# raw_input.net
KiCad netlist of a schematic drawn in Altium Designer
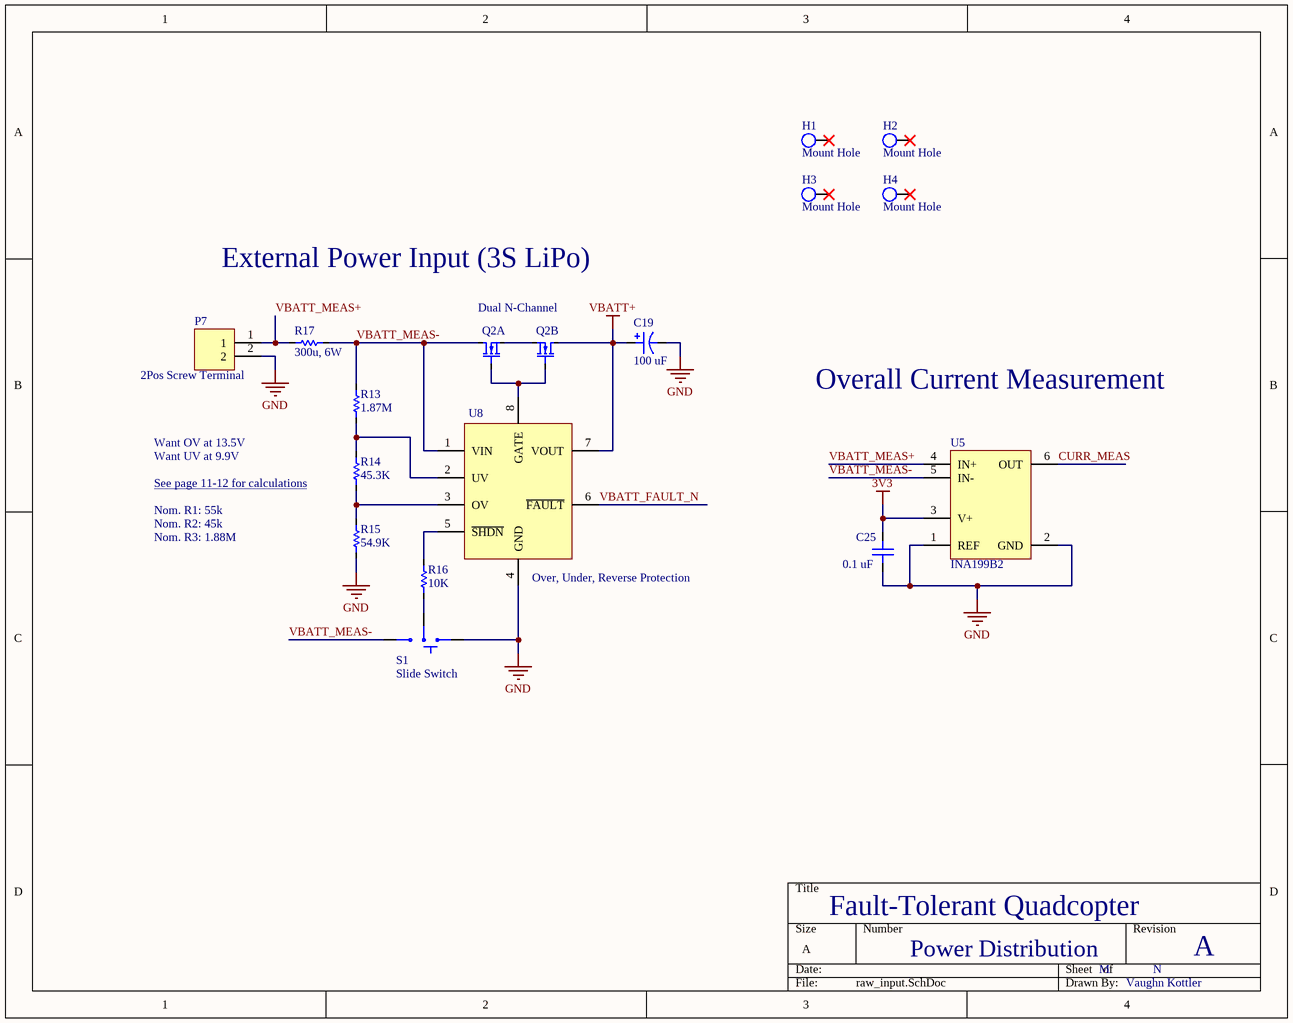
[diagram p0: raw_input.SchDoc]

(export (version "E")
  (design (tool "Eeschema 10.0.6"))
  (components
    (comp (ref "C19")
      (value "100 uF")
      (footprint "CAP-CAN-8.3x8.3")
      (description "±20%, 8.3mm x 8.3mm")
      (libsource (lib "passive") (part "CAP-CAN-100uF-25V"))
    )
    (comp (ref "C25")
      (value "0.1 uF")
      (footprint "CAP-CER-0805-SHORT")
      (description "10%, 0805")
      (libsource (lib "passive") (part "CAP-CER-0.1uF-25V"))
    )
    (comp (ref "H1")
      (value "Mount Hole")
      (footprint "4mm Mount Hole")
      (libsource (lib "connector") (part "Mount Hole"))
    )
    (comp (ref "H2")
      (value "Mount Hole")
      (footprint "4mm Mount Hole")
      (libsource (lib "connector") (part "Mount Hole"))
    )
    (comp (ref "H3")
      (value "Mount Hole")
      (footprint "4mm Mount Hole")
      (libsource (lib "connector") (part "Mount Hole"))
    )
    (comp (ref "H4")
      (value "Mount Hole")
      (footprint "4mm Mount Hole")
      (libsource (lib "connector") (part "Mount Hole"))
    )
    (comp (ref "P7")
      (value "2Pos Screw Terminal")
      (footprint "2Pos Screw Terminal")
      (description "0.2\" Pitch 1x2")
      (libsource (lib "connector") (part "2Pos Screw Terminal"))
    )
    (comp (ref "Q2")
      (value "Dual N-Channel")
      (footprint "PowerPAK 8x8L")
      (description "Dual N-Channel 40V 100A")
      (libsource (lib "ic") (part "SQJQ900E"))
    )
    (comp (ref "R13")
      (value "1.87M")
      (footprint "RES-0805")
      (description "1%, 0805")
      (libsource (lib "passive") (part "RES-1.87M-1/8W"))
    )
    (comp (ref "R14")
      (value "45.3K")
      (footprint "RES-0805")
      (description "1%, 0805")
      (libsource (lib "passive") (part "RES-45.3K-1/8W"))
    )
    (comp (ref "R15")
      (value "54.9K")
      (footprint "RES-0805")
      (description "1%, 0805")
      (libsource (lib "passive") (part "RES-54.9K-1/8W"))
    )
    (comp (ref "R16")
      (value "10K")
      (footprint "RES-0805")
      (description "0805")
      (libsource (lib "passive") (part "RES-10K-1/8W"))
    )
    (comp (ref "R17")
      (value "300u, 6W")
      (footprint "RES-SHNT-2512")
      (description "2512, 1%")
      (libsource (lib "passive") (part "RES-300u-6W"))
    )
    (comp (ref "S1")
      (value "Slide Switch")
      (footprint "SMT Slide Switch RA")
      (description "2mm Pitch")
      (libsource (lib "connector") (part "SMT Slide Switch"))
    )
    (comp (ref "U5")
      (value "INA199B2")
      (footprint "SC70")
      (description "100 V/V, Current-Shunt Monitor")
      (libsource (lib "ic") (part "INA199B2"))
    )
    (comp (ref "U8")
      (value "Over, Under, Reverse Protection")
      (footprint "SOT-23-8")
      (description "Overvoltage, Undervoltage and Reverse Supply Protection Controller")
      (libsource (lib "ic") (part "LTC4365"))
    )
  )
  (nets
    (net (code "1") (name "/CURR_MEAS") (class "Default")
      (node (ref "U5") (pin "6") (pinfunction "OUT_6") (pintype "passive"))
    )
    (net (code "2") (name "/VBATT_FAULT_N") (class "Default")
      (node (ref "U8") (pin "6") (pinfunction "~{FAULT}_6") (pintype "passive"))
    )
    (net (code "3") (name "/VBATT_MEAS+") (class "Default")
      (node (ref "P7") (pin "1") (pinfunction "1_1") (pintype "passive"))
      (node (ref "R17") (pin "1") (pinfunction "1_1") (pintype "passive"))
      (node (ref "U5") (pin "4") (pinfunction "IN+_4") (pintype "passive"))
    )
    (net (code "4") (name "/VBATT_MEAS-") (class "Default")
      (node (ref "Q2") (pin "D1") (pinfunction "D1_D1") (pintype "passive"))
      (node (ref "R13") (pin "2") (pinfunction "2_2") (pintype "passive"))
      (node (ref "R17") (pin "2") (pinfunction "2_2") (pintype "passive"))
      (node (ref "S1") (pin "3") (pinfunction "R_3") (pintype "passive"))
      (node (ref "U5") (pin "5") (pinfunction "IN-_5") (pintype "passive"))
      (node (ref "U8") (pin "1") (pinfunction "VIN_1") (pintype "passive"))
    )
    (net (code "5") (name "3V3") (class "Default")
      (node (ref "C25") (pin "2") (pinfunction "2_2") (pintype "passive"))
      (node (ref "U5") (pin "3") (pinfunction "V+_3") (pintype "passive"))
    )
    (net (code "6") (name "GND") (class "Default")
      (node (ref "C19") (pin "2") (pinfunction "2_2") (pintype "passive"))
      (node (ref "C25") (pin "1") (pinfunction "1_1") (pintype "passive"))
      (node (ref "P7") (pin "2") (pinfunction "2_2") (pintype "passive"))
      (node (ref "R15") (pin "1") (pinfunction "1_1") (pintype "passive"))
      (node (ref "S1") (pin "1") (pinfunction "L_1") (pintype "passive"))
      (node (ref "U5") (pin "1") (pinfunction "REF_1") (pintype "passive"))
      (node (ref "U5") (pin "2") (pinfunction "GND_2") (pintype "passive"))
      (node (ref "U8") (pin "4") (pinfunction "GND_4") (pintype "passive"))
    )
    (net (code "7") (name "Net-(Q2-PadS1)") (class "Default")
      (node (ref "Q2") (pin "S1") (pinfunction "S1_S1") (pintype "passive"))
      (node (ref "Q2") (pin "S2") (pinfunction "S2_S2") (pintype "passive"))
    )
    (net (code "8") (name "Net-(S1-COM)") (class "Default")
      (node (ref "R16") (pin "1") (pinfunction "1_1") (pintype "passive"))
      (node (ref "S1") (pin "2") (pinfunction "COM_2") (pintype "passive"))
    )
    (net (code "9") (name "Net-(U8-GATE)") (class "Default")
      (node (ref "Q2") (pin "G1") (pinfunction "G1_G1") (pintype "passive"))
      (node (ref "Q2") (pin "G2") (pinfunction "G2_G2") (pintype "passive"))
      (node (ref "U8") (pin "8") (pinfunction "GATE_8") (pintype "passive"))
    )
    (net (code "10") (name "Net-(U8-OV)") (class "Default")
      (node (ref "R14") (pin "1") (pinfunction "1_1") (pintype "passive"))
      (node (ref "R15") (pin "2") (pinfunction "2_2") (pintype "passive"))
      (node (ref "U8") (pin "3") (pinfunction "OV_3") (pintype "passive"))
    )
    (net (code "11") (name "Net-(U8-UV)") (class "Default")
      (node (ref "R13") (pin "1") (pinfunction "1_1") (pintype "passive"))
      (node (ref "R14") (pin "2") (pinfunction "2_2") (pintype "passive"))
      (node (ref "U8") (pin "2") (pinfunction "UV_2") (pintype "passive"))
    )
    (net (code "12") (name "Net-(U8-~{SHDN})") (class "Default")
      (node (ref "R16") (pin "2") (pinfunction "2_2") (pintype "passive"))
      (node (ref "U8") (pin "5") (pinfunction "~{SHDN}_5") (pintype "passive"))
    )
    (net (code "13") (name "VBATT+") (class "Default")
      (node (ref "C19") (pin "1") (pinfunction "1_1") (pintype "passive"))
      (node (ref "Q2") (pin "D2") (pinfunction "D2_D2") (pintype "passive"))
      (node (ref "U8") (pin "7") (pinfunction "VOUT_7") (pintype "passive"))
    )
    (net (code "14") (name "unconnected-(H1-PadH)") (class "Default")
      (node (ref "H1") (pin "H") (pinfunction "H_H") (pintype "passive+no_connect"))
    )
    (net (code "15") (name "unconnected-(H2-PadH)") (class "Default")
      (node (ref "H2") (pin "H") (pinfunction "H_H") (pintype "passive+no_connect"))
    )
    (net (code "16") (name "unconnected-(H3-PadH)") (class "Default")
      (node (ref "H3") (pin "H") (pinfunction "H_H") (pintype "passive+no_connect"))
    )
    (net (code "17") (name "unconnected-(H4-PadH)") (class "Default")
      (node (ref "H4") (pin "H") (pinfunction "H_H") (pintype "passive+no_connect"))
    )
  )
)
